# gps.net
KiCad netlist of a schematic drawn in EAGLE
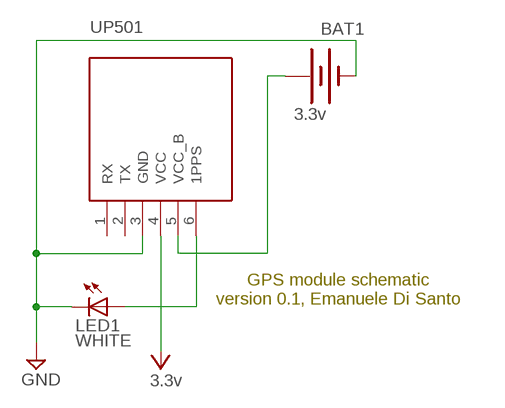
[diagram p0: schematic, sheet 1]

(export (version "E")
  (design (tool "Eeschema 10.0.6"))
  (components
    (comp (ref "BAT1")
      (value "3.3v")
      (footprint "eagle-import:BATTCON_12MM")
      (libsource (lib "eagle-import") (part "BATTERY12MM"))
    )
    (comp (ref "LED1")
      (value "WHITE")
      (footprint "eagle-import:CHIPLED_0805")
      (libsource (lib "eagle-import") (part "LEDCHIPLED_0805"))
    )
    (comp (ref "U1")
      (value "UP501")
      (footprint "eagle-import:1X06")
      (libsource (lib "eagle-import") (part "UP501"))
    )
  )
  (nets
    (net (code "1") (name "3.3v") (class "Default")
      (node (ref "U1") (pin "4") (pinfunction "VCC_4") (pintype "bidirectional"))
    )
    (net (code "2") (name "GND") (class "Default")
      (node (ref "BAT1") (pin "GND") (pinfunction "-_GND") (pintype "power_in"))
      (node (ref "LED1") (pin "C") (pinfunction "C_C") (pintype "passive"))
      (node (ref "U1") (pin "3") (pinfunction "GND_3") (pintype "bidirectional"))
    )
    (net (code "3") (name "Net-(BAT1-+)") (class "Default")
      (node (ref "BAT1") (pin "PWR@1") (pinfunction "+_PWR@1") (pintype "power_in"))
      (node (ref "U1") (pin "5") (pinfunction "VCC_B_5") (pintype "bidirectional"))
    )
    (net (code "4") (name "Net-(U1-1PPS)") (class "Default")
      (node (ref "LED1") (pin "A") (pinfunction "A_A") (pintype "passive"))
      (node (ref "U1") (pin "6") (pinfunction "1PPS_6") (pintype "bidirectional"))
    )
    (net (code "5") (name "unconnected-(U1-RX-Pad1)") (class "Default")
      (node (ref "U1") (pin "1") (pinfunction "RX_1") (pintype "bidirectional"))
    )
    (net (code "6") (name "unconnected-(U1-TX-Pad2)") (class "Default")
      (node (ref "U1") (pin "2") (pinfunction "TX_2") (pintype "bidirectional"))
    )
  )
)
